# DRV8424.net
KiCad netlist of a schematic drawn in Altium Designer
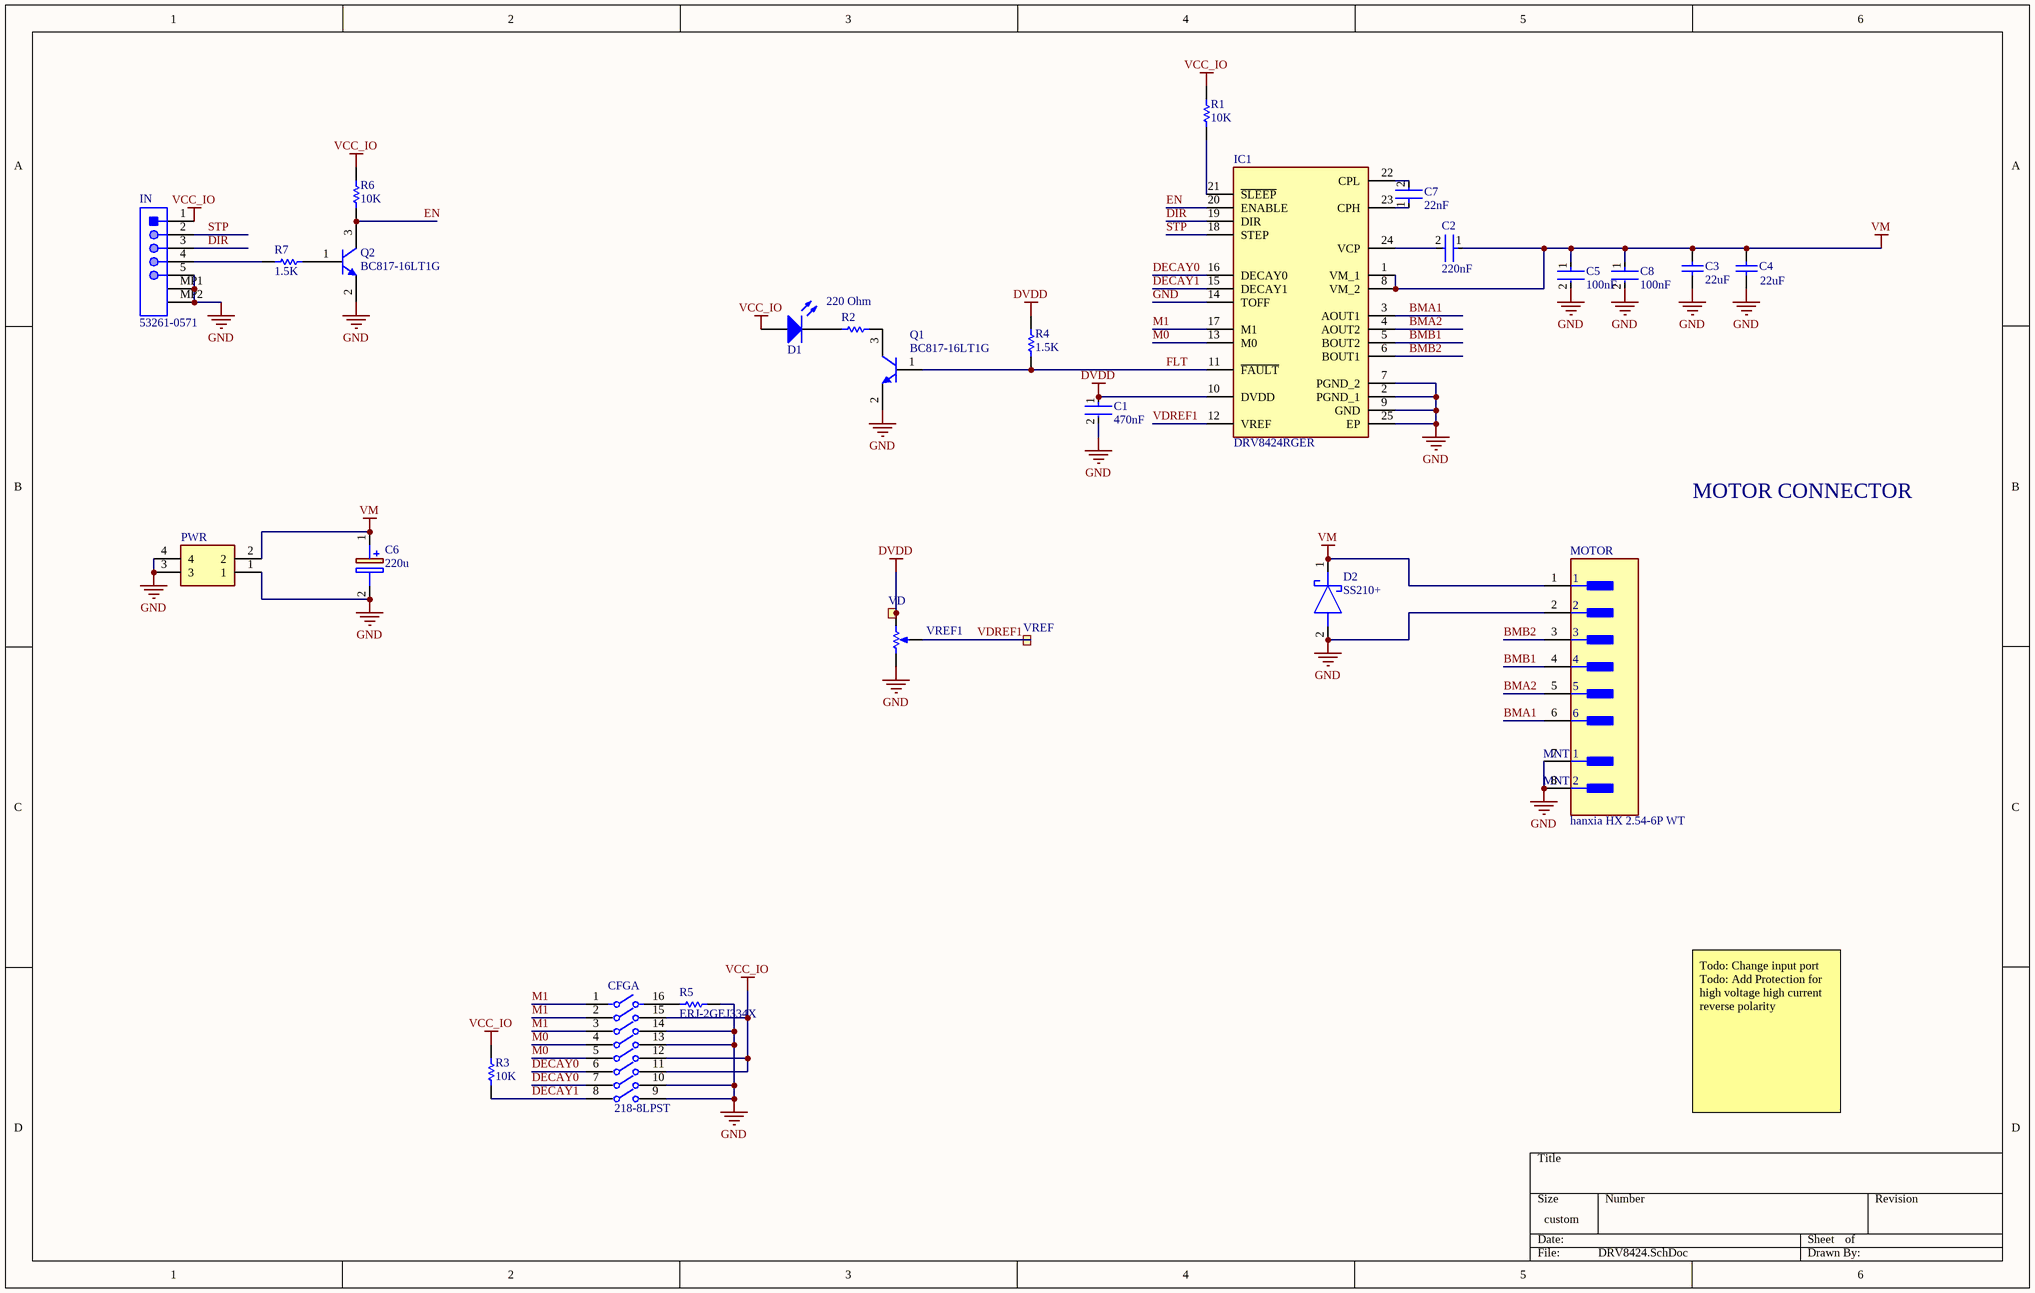
[diagram p0: DRV8424.SchDoc]

(export (version "E")
  (design (tool "Eeschema 10.0.6"))
  (components
    (comp (ref "C1")
      (value "C1005X5R1V474K050BC")
      (footprint "FP-C1005-050-0_05-IPC_B")
      (description "Multilayer Ceramic Capacitors 470nF ±10% 35V X5R SMD 0402")
      (fields (field (name "TOLERANCE") "10%") (field (name "CAPACITANCE") "470nF"))
      (libsource (lib "Altium Content Vault") (part "b4654b650e69147ec39a6b967a45e02"))
    )
    (comp (ref "C2")
      (value "C1005X7R1V224K050BC")
      (footprint "FP-C1005-050-0_05-IPC_B")
      (description "Multilayer Ceramic Capacitors 220nF ±10% 35V X7R SMD 0402")
      (fields (field (name "CAPACITANCE") "220nF") (field (name "TOLERANCE") "10%"))
      (libsource (lib "Altium Content Vault") (part "b4654b650e69147ec39a6b967a45e02"))
    )
    (comp (ref "C3")
      (value "22uF")
      (footprint "C1206")
      (description "Capacitor")
      (fields (field (name "DESIGNER") "Parsa Malekpour"))
      (libsource (lib "UserPKG") (part "Cap"))
    )
    (comp (ref "C4")
      (value "22uF")
      (footprint "C1206")
      (description "Capacitor")
      (fields (field (name "DESIGNER") "Parsa Malekpour"))
      (libsource (lib "UserPKG") (part "Cap"))
    )
    (comp (ref "C5")
      (value "C1005X7R1H104K050BB")
      (footprint "FP-C1005-050-0_05-IPC_C")
      (description "Multilayer Ceramic Capacitors 100nF ±10% 50V X7R SMD 0402")
      (fields
        (field (name "VOLTAGE") "50V")
        (field (name "CAPACITANCE") "100nF")
        (field (name "TOLERANCE") "10%")
      )
      (libsource (lib "Altium Content Vault") (part "b4654b650e69147ec39a6b967a45e02"))
    )
    (comp (ref "C6")
      (value "220u")
      (footprint "SamacSys:CAPAE1030X1050N")
      (description "Capacitor Polarised")
      (fields (field (name "MANUFACTURER_PART_NUMBER") "VZH221M1HTR-1010L"))
      (libsource (lib "SamacSys") (part "VZH221M1HTR-1010L"))
    )
    (comp (ref "C7")
      (value "C1005X7R1H223K050BB")
      (footprint "FP-C1005-050-0_05-IPC_C")
      (description "Multilayer Ceramic Capacitors 22nF ±10% 50V X7R SMD 0402")
      (fields (field (name "CAPACITANCE") "22nF") (field (name "TOLERANCE") "10%"))
      (libsource (lib "Altium Content Vault") (part "b4654b650e69147ec39a6b967a45e02"))
    )
    (comp (ref "C8")
      (value "C1005X7R1H104K050BB")
      (footprint "FP-C1005-050-0_05-IPC_C")
      (description "Multilayer Ceramic Capacitors 100nF ±10% 50V X7R SMD 0402")
      (fields
        (field (name "VOLTAGE") "50V")
        (field (name "CAPACITANCE") "100nF")
        (field (name "TOLERANCE") "10%")
      )
      (libsource (lib "Altium Content Vault") (part "b4654b650e69147ec39a6b967a45e02"))
    )
    (comp (ref "CFG")
      (value "218-8LPST")
      (footprint "FP-218-8LPST-MFG")
      (description "SWITCH SLIDE DIP SPST 25MA 24V")
      (libsource (lib "Altium Content Vault") (part "c442af63ff53b934e43635f80d8690e"))
    )
    (comp (ref "D1") (value "LED") (footprint "led-0603") (libsource (lib "ParsaLibrary") (part "LED")))
    (comp (ref "D2")
      (value "SS210+")
      (footprint "SamacSys:DIOM5336X244N")
      (description "Schottky Diode")
      (libsource (lib "*") (part "SS210+"))
    )
    (comp (ref "IC1")
      (value "DRV8424RGER")
      (footprint "SamacSys:QFN50P400X400X100-25N-D")
      (description "Integrated Circuit")
      (fields (field (name "MOUSER PART NUMBER") "595-DRV8424RGER"))
      (libsource (lib "SamacSys") (part "DRV8424RGER"))
    )
    (comp (ref "IN")
      (value "53261-0571")
      (footprint "MOLX-52361-0571-5_V")
      (description "Male Header, Pitch 1.25 mm, 1 x 5 Position, Height 3.4 mm, RoHS, Tape and Reel")
      (fields (field (name "MANUFACTURER") "Molex"))
      (libsource (lib "Altium Content Vault") (part "CN-1P-2M-R5"))
    )
    (comp (ref "MOTOR")
      (value "hanxia HX 2.54-6P WT")
      (footprint "FP-S6B-XH-SM4-TB_LF_SN-MFG")
      (description "CONN HEADER SMD R/A 6POS 2.5MM - S6B-XH-SM4-TB(LF)(SN)")
      (libsource (lib "Altium Content Vault") (part "ed24c53d9ba001d1a2a686240a95171"))
    )
    (comp (ref "PWR")
      (value "SHOU HAN 2.54-2P WT")
      (footprint "A2501WF-02A")
      (description "Connector")
      (fields
        (field (name "MANUFACTURER_PART_NUMBER") "1778764")
        (field (name "MOUSER PART NUMBER") "651-1778764")
      )
      (libsource (lib "*") (part "1778764"))
    )
    (comp (ref "Q1")
      (value "BC817-16LT1G")
      (footprint "SOT-23")
      (description "General Purpose Transistor, NPN Silicon, 3-Pin SOT-23, Pb-Free, Tape and Reel")
      (fields (field (name "MANUFACTURER") "On Semiconductor"))
      (libsource (lib "ParsaLibrary") (part "ONSC-NPN-B1E2C3-3"))
    )
    (comp (ref "Q2")
      (value "BC817-16LT1G")
      (footprint "SOT-23")
      (description "General Purpose Transistor, NPN Silicon, 3-Pin SOT-23, Pb-Free, Tape and Reel")
      (fields (field (name "MANUFACTURER") "On Semiconductor"))
      (libsource (lib "ParsaLibrary") (part "ONSC-NPN-B1E2C3-3"))
    )
    (comp (ref "R1")
      (value "ERJ-2GEJ103X")
      (footprint "RESC1005X40X25ML05T05")
      (fields (field (name "MANUFACTURER") "Panasonic") (field (name "RESISTANCE") "10K"))
      (libsource (lib "Altium Content Vault") (part "RES"))
    )
    (comp (ref "R2")
      (value "ERJ-2GEJ221X")
      (footprint "RESC1005X40X25LL05T05")
      (description "Chip Resistor, 220 Ohm, +/- 5%, 100 mW, -55 to 155 degC, 0402 (1005 Metric), RoHS, Tape and Reel")
      (fields
        (field (name "MANUFACTURER") "Basic Passives")
        (field (name "TOLERANCE") "5%")
        (field (name "RESISTANCE") "220 Ohm")
      )
      (libsource (lib "Altium Content Vault") (part "RES-2"))
    )
    (comp (ref "R3")
      (value "ERJ-2GEJ103X")
      (footprint "RESC1005X40X25ML05T05")
      (fields (field (name "MANUFACTURER") "Panasonic") (field (name "RESISTANCE") "10K"))
      (libsource (lib "Altium Content Vault") (part "RES"))
    )
    (comp (ref "R4")
      (value "ERJ-2GEJ152X")
      (footprint "RESC1005X40X25NL05T05")
      (fields (field (name "MANUFACTURER") "Panasonic") (field (name "RESISTANCE") "1.5K"))
      (libsource (lib "Altium Content Vault") (part "RES"))
    )
    (comp (ref "R5")
      (value "ERJ-2GEJ334X")
      (footprint "RESC1005X40X25ML05T05")
      (fields (field (name "MANUFACTURER") "Panasonic"))
      (libsource (lib "Altium Content Vault") (part "RES"))
    )
    (comp (ref "R6")
      (value "ERJ-2GEJ103X")
      (footprint "RESC1005X40X25ML05T05")
      (fields (field (name "MANUFACTURER") "Panasonic") (field (name "RESISTANCE") "10K"))
      (libsource (lib "Altium Content Vault") (part "RES"))
    )
    (comp (ref "R7")
      (value "ERJ-2GEJ152X")
      (footprint "RESC1005X40X25NL05T05")
      (fields (field (name "MANUFACTURER") "Panasonic") (field (name "RESISTANCE") "1.5K"))
      (libsource (lib "Altium Content Vault") (part "RES"))
    )
    (comp (ref "VD")
      (value "Ø1.5mm,SMD")
      (footprint "TP_SMD_Ø1.5mm")
      (description "1.5mm circular SMD testpad")
      (fields
        (field (name "PART NUMBER") "TP_SMD_Ø1.5MM")
        (field (name "MANUFACTURER") "Nordic Semiconductor")
      )
      (libsource (lib "ParsaLibrary") (part "TP_SMD_Ø1.5MM"))
    )
    (comp (ref "VREF")
      (value "Ø1.5mm,SMD")
      (footprint "TP_SMD_Ø1.5mm")
      (description "1.5mm circular SMD testpad")
      (fields
        (field (name "PART NUMBER") "TP_SMD_Ø1.5MM")
        (field (name "MANUFACTURER") "Nordic Semiconductor")
      )
      (libsource (lib "ParsaLibrary") (part "TP_SMD_Ø1.5MM"))
    )
    (comp (ref "VREF1")
      (value "POT 20k")
      (footprint "POT-SMD")
      (description "Varible Resistor")
      (libsource (lib "ParsaLibrary") (part "R-POT"))
    )
  )
  (nets
    (net (code "1") (name "/BMA1") (class "Default")
      (node (ref "IC1") (pin "3") (pinfunction "AOUT1_3") (pintype "passive"))
      (node (ref "MOTOR") (pin "6") (pinfunction "6_6") (pintype "passive"))
    )
    (net (code "2") (name "/BMA2") (class "Default")
      (node (ref "IC1") (pin "4") (pinfunction "AOUT2_4") (pintype "passive"))
      (node (ref "MOTOR") (pin "5") (pinfunction "5_5") (pintype "passive"))
    )
    (net (code "3") (name "/BMB1") (class "Default")
      (node (ref "IC1") (pin "5") (pinfunction "BOUT2_5") (pintype "passive"))
      (node (ref "MOTOR") (pin "4") (pinfunction "4_4") (pintype "passive"))
    )
    (net (code "4") (name "/BMB2") (class "Default")
      (node (ref "IC1") (pin "6") (pinfunction "BOUT1_6") (pintype "passive"))
      (node (ref "MOTOR") (pin "3") (pinfunction "3_3") (pintype "passive"))
    )
    (net (code "5") (name "/DECAY0") (class "Default")
      (node (ref "CFG") (pin "6") (pinfunction "6_6") (pintype "passive"))
      (node (ref "CFG") (pin "7") (pinfunction "7_7") (pintype "passive"))
      (node (ref "IC1") (pin "16") (pinfunction "DECAY0_16") (pintype "passive"))
    )
    (net (code "6") (name "/DECAY1") (class "Default")
      (node (ref "CFG") (pin "8") (pinfunction "8_8") (pintype "passive"))
      (node (ref "IC1") (pin "15") (pinfunction "DECAY1_15") (pintype "passive"))
      (node (ref "R3") (pin "2") (pinfunction "2_2") (pintype "passive"))
    )
    (net (code "7") (name "/DIR") (class "Default")
      (node (ref "IC1") (pin "19") (pinfunction "DIR_19") (pintype "passive"))
      (node (ref "IN") (pin "3") (pinfunction "3_3") (pintype "passive"))
    )
    (net (code "8") (name "/EN") (class "Default")
      (node (ref "IC1") (pin "20") (pinfunction "ENABLE_20") (pintype "passive"))
      (node (ref "Q2") (pin "3") (pinfunction "C_3") (pintype "passive"))
      (node (ref "R6") (pin "2") (pinfunction "2_2") (pintype "passive"))
    )
    (net (code "9") (name "/FLT") (class "Default")
      (node (ref "IC1") (pin "11") (pinfunction "~{FAULT}_11") (pintype "passive"))
      (node (ref "Q1") (pin "1") (pinfunction "B_1") (pintype "passive"))
      (node (ref "R4") (pin "2") (pinfunction "2_2") (pintype "passive"))
    )
    (net (code "10") (name "/M0") (class "Default")
      (node (ref "CFG") (pin "4") (pinfunction "4_4") (pintype "passive"))
      (node (ref "CFG") (pin "5") (pinfunction "5_5") (pintype "passive"))
      (node (ref "IC1") (pin "13") (pinfunction "M0_13") (pintype "passive"))
    )
    (net (code "11") (name "/M1") (class "Default")
      (node (ref "CFG") (pin "1") (pinfunction "1_1") (pintype "passive"))
      (node (ref "CFG") (pin "2") (pinfunction "2_2") (pintype "passive"))
      (node (ref "CFG") (pin "3") (pinfunction "3_3") (pintype "passive"))
      (node (ref "IC1") (pin "17") (pinfunction "M1_17") (pintype "passive"))
    )
    (net (code "12") (name "/STP") (class "Default")
      (node (ref "IC1") (pin "18") (pinfunction "STEP_18") (pintype "passive"))
      (node (ref "IN") (pin "2") (pinfunction "2_2") (pintype "passive"))
    )
    (net (code "13") (name "/VDREF1") (class "Default")
      (node (ref "IC1") (pin "12") (pinfunction "VREF_12") (pintype "passive"))
      (node (ref "VREF") (pin "1") (pinfunction "1_1") (pintype "passive"))
      (node (ref "VREF1") (pin "3") (pinfunction "TAP_3") (pintype "passive"))
    )
    (net (code "14") (name "DVDD") (class "Default")
      (node (ref "C1") (pin "1") (pinfunction "1_1") (pintype "passive"))
      (node (ref "IC1") (pin "10") (pinfunction "DVDD_10") (pintype "passive"))
      (node (ref "R4") (pin "1") (pinfunction "1_1") (pintype "passive"))
      (node (ref "VD") (pin "1") (pinfunction "1_1") (pintype "passive"))
      (node (ref "VREF1") (pin "2") (pinfunction "BOT_2") (pintype "passive"))
    )
    (net (code "15") (name "GND") (class "Default")
      (node (ref "C1") (pin "2") (pinfunction "2_2") (pintype "passive"))
      (node (ref "C3") (pin "1") (pinfunction "1_1") (pintype "passive"))
      (node (ref "C4") (pin "1") (pinfunction "1_1") (pintype "passive"))
      (node (ref "C5") (pin "2") (pinfunction "2_2") (pintype "passive"))
      (node (ref "C6") (pin "2") (pinfunction "-_2") (pintype "passive"))
      (node (ref "C8") (pin "2") (pinfunction "2_2") (pintype "passive"))
      (node (ref "CFG") (pin "10") (pinfunction "10_10") (pintype "passive"))
      (node (ref "CFG") (pin "13") (pinfunction "13_13") (pintype "passive"))
      (node (ref "CFG") (pin "14") (pinfunction "14_14") (pintype "passive"))
      (node (ref "CFG") (pin "9") (pinfunction "9_9") (pintype "passive"))
      (node (ref "D2") (pin "2") (pinfunction "A_2") (pintype "passive"))
      (node (ref "IC1") (pin "14") (pinfunction "TOFF_14") (pintype "passive"))
      (node (ref "IC1") (pin "2") (pinfunction "PGND_1_2") (pintype "passive"))
      (node (ref "IC1") (pin "25") (pinfunction "EP_25") (pintype "passive"))
      (node (ref "IC1") (pin "7") (pinfunction "PGND_2_7") (pintype "passive"))
      (node (ref "IC1") (pin "9") (pinfunction "GND_9") (pintype "passive"))
      (node (ref "IN") (pin "5") (pinfunction "5_5") (pintype "passive"))
      (node (ref "IN") (pin "MP1") (pinfunction "MP1_MP1") (pintype "passive"))
      (node (ref "IN") (pin "MP2") (pinfunction "MP2_MP2") (pintype "passive"))
      (node (ref "MOTOR") (pin "2") (pinfunction "2_2") (pintype "passive"))
      (node (ref "MOTOR") (pin "7") (pinfunction "MNT_1_7") (pintype "passive"))
      (node (ref "MOTOR") (pin "8") (pinfunction "MNT_2_8") (pintype "passive"))
      (node (ref "PWR") (pin "1") (pinfunction "1_1") (pintype "passive"))
      (node (ref "PWR") (pin "3") (pinfunction "3_3") (pintype "passive"))
      (node (ref "PWR") (pin "4") (pinfunction "4_4") (pintype "passive"))
      (node (ref "Q1") (pin "2") (pinfunction "E_2") (pintype "passive"))
      (node (ref "Q2") (pin "2") (pinfunction "E_2") (pintype "passive"))
      (node (ref "R5") (pin "2") (pinfunction "2_2") (pintype "passive"))
      (node (ref "VREF1") (pin "1") (pinfunction "TOP_1") (pintype "passive"))
    )
    (net (code "16") (name "Net-(CFG-Pad16)") (class "Default")
      (node (ref "CFG") (pin "16") (pinfunction "16_16") (pintype "passive"))
      (node (ref "R5") (pin "1") (pinfunction "1_1") (pintype "passive"))
    )
    (net (code "17") (name "Net-(D1-K)") (class "Default")
      (node (ref "D1") (pin "2") (pinfunction "K_2") (pintype "passive"))
      (node (ref "R2") (pin "1") (pinfunction "1_1") (pintype "passive"))
    )
    (net (code "18") (name "Net-(IC1-CPH)") (class "Default")
      (node (ref "C7") (pin "1") (pinfunction "1_1") (pintype "passive"))
      (node (ref "IC1") (pin "23") (pinfunction "CPH_23") (pintype "passive"))
    )
    (net (code "19") (name "Net-(IC1-CPL)") (class "Default")
      (node (ref "C7") (pin "2") (pinfunction "2_2") (pintype "passive"))
      (node (ref "IC1") (pin "22") (pinfunction "CPL_22") (pintype "passive"))
    )
    (net (code "20") (name "Net-(IC1-VCP)") (class "Default")
      (node (ref "C2") (pin "2") (pinfunction "2_2") (pintype "passive"))
      (node (ref "IC1") (pin "24") (pinfunction "VCP_24") (pintype "passive"))
    )
    (net (code "21") (name "Net-(IC1-~{SLEEP})") (class "Default")
      (node (ref "IC1") (pin "21") (pinfunction "~{SLEEP}_21") (pintype "passive"))
      (node (ref "R1") (pin "2") (pinfunction "2_2") (pintype "passive"))
    )
    (net (code "22") (name "Net-(IN-Pad4)") (class "Default")
      (node (ref "IN") (pin "4") (pinfunction "4_4") (pintype "passive"))
      (node (ref "R7") (pin "1") (pinfunction "1_1") (pintype "passive"))
    )
    (net (code "23") (name "Net-(Q1-C)") (class "Default")
      (node (ref "Q1") (pin "3") (pinfunction "C_3") (pintype "passive"))
      (node (ref "R2") (pin "2") (pinfunction "2_2") (pintype "passive"))
    )
    (net (code "24") (name "Net-(Q2-B)") (class "Default")
      (node (ref "Q2") (pin "1") (pinfunction "B_1") (pintype "passive"))
      (node (ref "R7") (pin "2") (pinfunction "2_2") (pintype "passive"))
    )
    (net (code "25") (name "VCC_IO") (class "Default")
      (node (ref "CFG") (pin "11") (pinfunction "11_11") (pintype "passive"))
      (node (ref "CFG") (pin "12") (pinfunction "12_12") (pintype "passive"))
      (node (ref "CFG") (pin "15") (pinfunction "15_15") (pintype "passive"))
      (node (ref "D1") (pin "1") (pinfunction "A_1") (pintype "passive"))
      (node (ref "IN") (pin "1") (pinfunction "1_1") (pintype "passive"))
      (node (ref "R1") (pin "1") (pinfunction "1_1") (pintype "passive"))
      (node (ref "R3") (pin "1") (pinfunction "1_1") (pintype "passive"))
      (node (ref "R6") (pin "1") (pinfunction "1_1") (pintype "passive"))
    )
    (net (code "26") (name "VM") (class "Default")
      (node (ref "C2") (pin "1") (pinfunction "1_1") (pintype "passive"))
      (node (ref "C3") (pin "2") (pinfunction "2_2") (pintype "passive"))
      (node (ref "C4") (pin "2") (pinfunction "2_2") (pintype "passive"))
      (node (ref "C5") (pin "1") (pinfunction "1_1") (pintype "passive"))
      (node (ref "C6") (pin "1") (pinfunction "+_1") (pintype "passive"))
      (node (ref "C8") (pin "1") (pinfunction "1_1") (pintype "passive"))
      (node (ref "D2") (pin "1") (pinfunction "K_1") (pintype "passive"))
      (node (ref "IC1") (pin "1") (pinfunction "VM_1_1") (pintype "passive"))
      (node (ref "IC1") (pin "8") (pinfunction "VM_2_8") (pintype "passive"))
      (node (ref "MOTOR") (pin "1") (pinfunction "1_1") (pintype "passive"))
      (node (ref "PWR") (pin "2") (pinfunction "2_2") (pintype "passive"))
    )
  )
)
